# SEGMENTOVKA_I2C.net
KiCad netlist of a schematic drawn in EAGLE
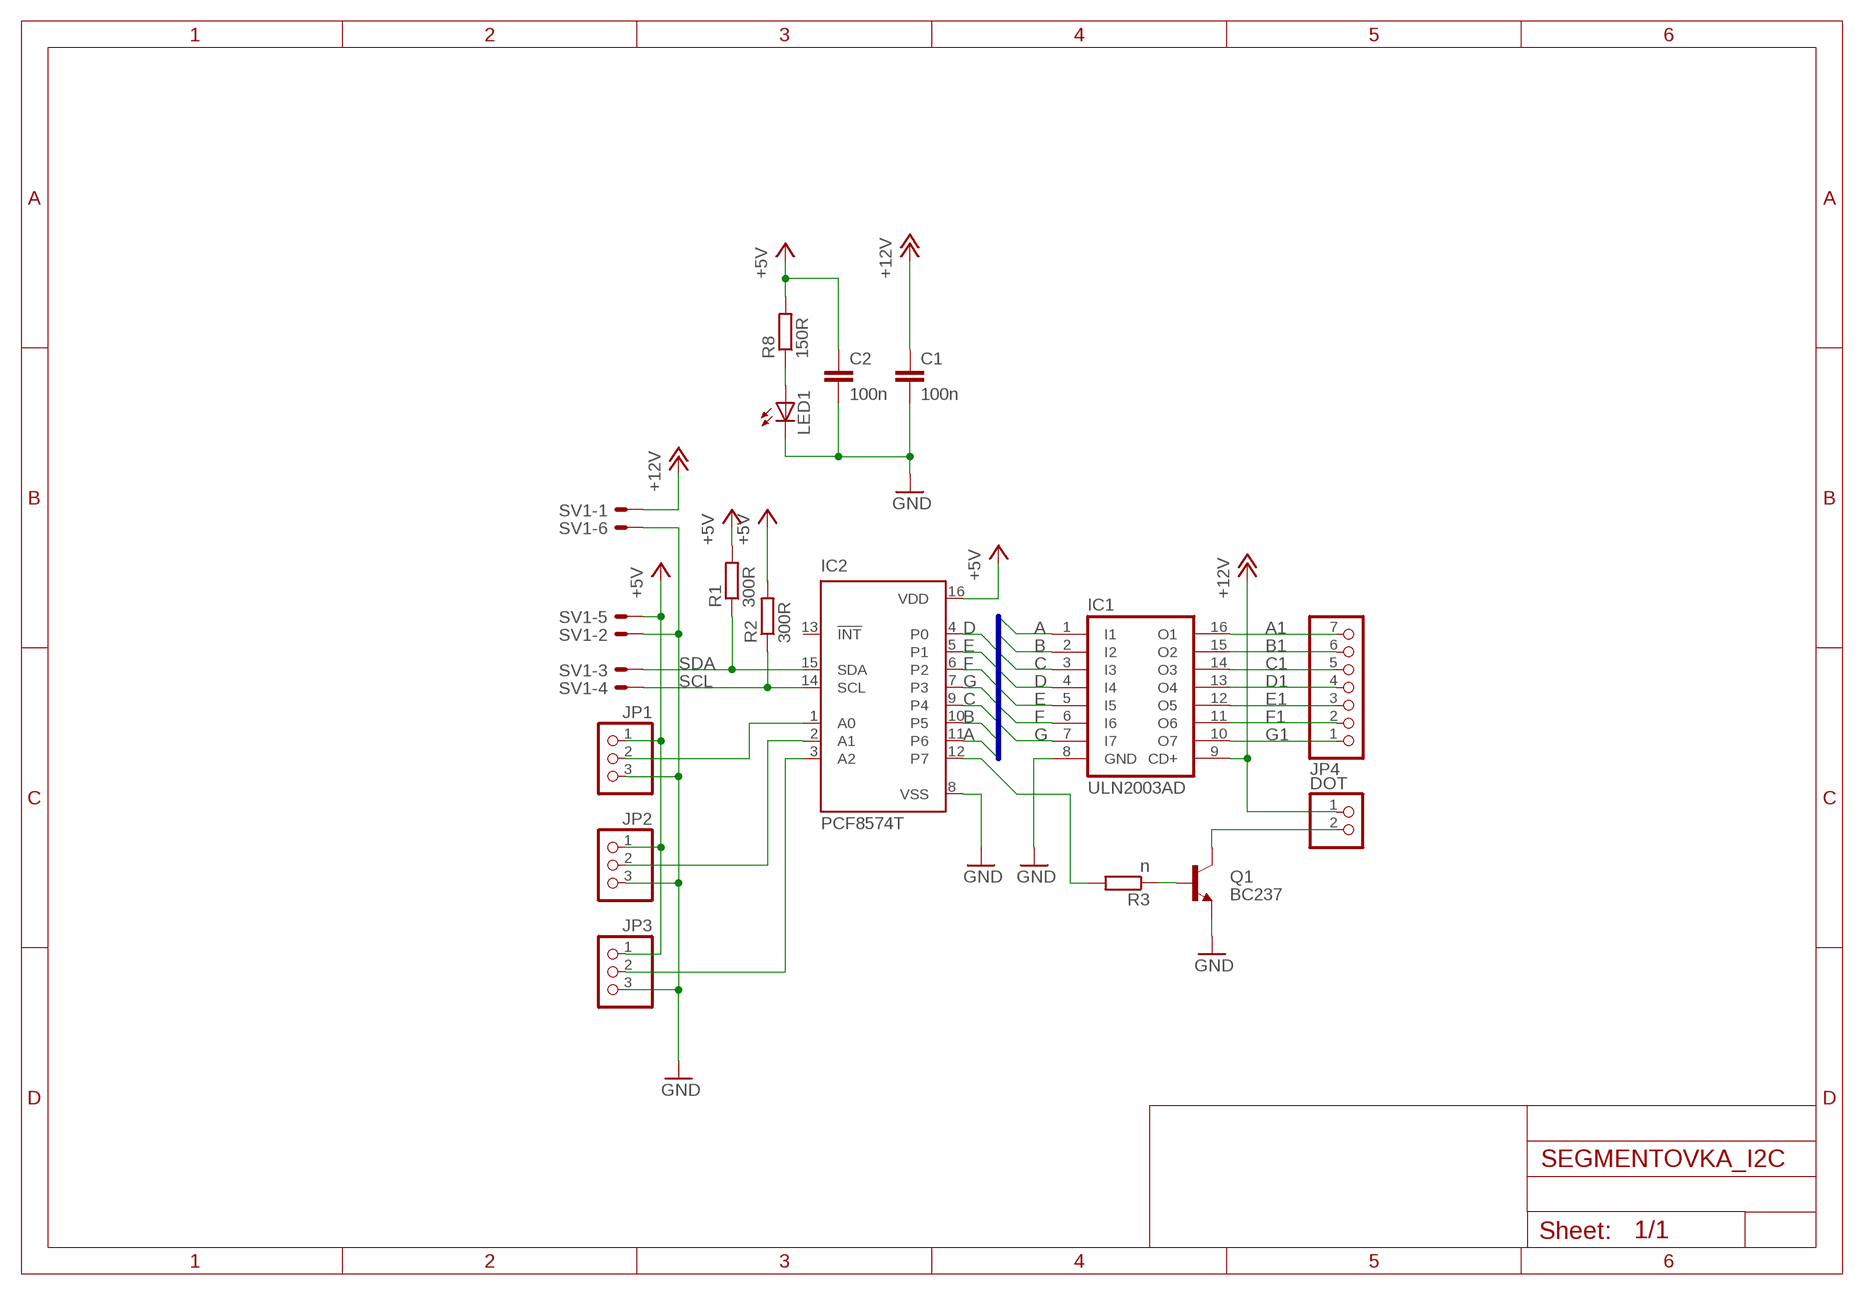
[diagram p0: schematic, sheet 1]

(export (version "E")
  (design (tool "Eeschema 10.0.6"))
  (components
    (comp (ref "C1")
      (value "100n")
      (footprint "eagle-import:C0603")
      (libsource (lib "eagle-import") (part "C-EUC0603"))
    )
    (comp (ref "C2")
      (value "100n")
      (footprint "eagle-import:C0603")
      (libsource (lib "eagle-import") (part "C-EUC0603"))
    )
    (comp (ref "DOT")
      (value "PINHD-1X2")
      (footprint "eagle-import:1X02")
      (libsource (lib "eagle-import") (part "PINHD-1X2"))
    )
    (comp (ref "IC1")
      (value "ULN2003AD")
      (footprint "eagle-import:SO16")
      (libsource (lib "eagle-import") (part "ULN2003AD"))
    )
    (comp (ref "IC2")
      (value "PCF8574T")
      (footprint "eagle-import:SO16W")
      (fields (field (name "MPN") "PCF8574T/3,512"))
      (libsource (lib "eagle-import") (part "PCF8574T"))
    )
    (comp (ref "JP1")
      (value "PINHD-1X3")
      (footprint "eagle-import:1X03")
      (libsource (lib "eagle-import") (part "PINHD-1X3"))
    )
    (comp (ref "JP2")
      (value "PINHD-1X3")
      (footprint "eagle-import:1X03")
      (libsource (lib "eagle-import") (part "PINHD-1X3"))
    )
    (comp (ref "JP3")
      (value "PINHD-1X3")
      (footprint "eagle-import:1X03")
      (libsource (lib "eagle-import") (part "PINHD-1X3"))
    )
    (comp (ref "JP4")
      (value "PINHD-1X7")
      (footprint "eagle-import:1X07")
      (libsource (lib "eagle-import") (part "PINHD-1X7"))
    )
    (comp (ref "LED1")
      (value "LEDCHIP-LED0603")
      (footprint "eagle-import:CHIP-LED0603")
      (libsource (lib "eagle-import") (part "LEDCHIP-LED0603"))
    )
    (comp (ref "Q1")
      (value "BC237")
      (footprint "eagle-import:TO92")
      (libsource (lib "eagle-import") (part "BC237"))
    )
    (comp (ref "R1")
      (value "300R")
      (footprint "eagle-import:R0603")
      (libsource (lib "eagle-import") (part "R-EU_R0603"))
    )
    (comp (ref "R2")
      (value "300R")
      (footprint "eagle-import:R0603")
      (libsource (lib "eagle-import") (part "R-EU_R0603"))
    )
    (comp (ref "R3")
      (value "n")
      (footprint "eagle-import:R0603")
      (libsource (lib "eagle-import") (part "R-EU_R0603"))
    )
    (comp (ref "R8")
      (value "150R")
      (footprint "eagle-import:R0603")
      (libsource (lib "eagle-import") (part "R-EU_R0603"))
    )
    (comp (ref "SV1")
      (value "ML6E")
      (footprint "eagle-import:ML6")
      (libsource (lib "eagle-import") (part "ML6E"))
    )
  )
  (nets
    (net (code "1") (name "+5V") (class "Default")
      (node (ref "C2") (pin "1") (pinfunction "1_1") (pintype "passive"))
      (node (ref "IC2") (pin "16") (pinfunction "VDD_16") (pintype "power_in"))
      (node (ref "JP1") (pin "1") (pinfunction "1_1") (pintype "passive"))
      (node (ref "JP2") (pin "1") (pinfunction "1_1") (pintype "passive"))
      (node (ref "JP3") (pin "1") (pinfunction "1_1") (pintype "passive"))
      (node (ref "R1") (pin "2") (pinfunction "2_2") (pintype "passive"))
      (node (ref "R2") (pin "2") (pinfunction "2_2") (pintype "passive"))
      (node (ref "R8") (pin "2") (pinfunction "2_2") (pintype "passive"))
      (node (ref "SV1") (pin "5") (pinfunction "S_5") (pintype "passive"))
    )
    (net (code "2") (name "+12V") (class "Default")
      (node (ref "C1") (pin "1") (pinfunction "1_1") (pintype "passive"))
      (node (ref "DOT") (pin "1") (pinfunction "1_1") (pintype "passive"))
      (node (ref "IC1") (pin "9") (pinfunction "CD+_9") (pintype "passive"))
      (node (ref "SV1") (pin "1") (pinfunction "S_1") (pintype "passive"))
    )
    (net (code "3") (name "/A") (class "Default")
      (node (ref "IC1") (pin "1") (pinfunction "I1_1") (pintype "input"))
      (node (ref "IC2") (pin "11") (pinfunction "P6_11") (pintype "bidirectional"))
    )
    (net (code "4") (name "/A1") (class "Default")
      (node (ref "IC1") (pin "16") (pinfunction "O1_16") (pintype "open_collector"))
      (node (ref "JP4") (pin "7") (pinfunction "7_7") (pintype "passive"))
    )
    (net (code "5") (name "/B") (class "Default")
      (node (ref "IC1") (pin "2") (pinfunction "I2_2") (pintype "input"))
      (node (ref "IC2") (pin "10") (pinfunction "P5_10") (pintype "bidirectional"))
    )
    (net (code "6") (name "/B1") (class "Default")
      (node (ref "IC1") (pin "15") (pinfunction "O2_15") (pintype "open_collector"))
      (node (ref "JP4") (pin "6") (pinfunction "6_6") (pintype "passive"))
    )
    (net (code "7") (name "/C") (class "Default")
      (node (ref "IC1") (pin "3") (pinfunction "I3_3") (pintype "input"))
      (node (ref "IC2") (pin "9") (pinfunction "P4_9") (pintype "bidirectional"))
    )
    (net (code "8") (name "/C1") (class "Default")
      (node (ref "IC1") (pin "14") (pinfunction "O3_14") (pintype "open_collector"))
      (node (ref "JP4") (pin "5") (pinfunction "5_5") (pintype "passive"))
    )
    (net (code "9") (name "/D") (class "Default")
      (node (ref "IC1") (pin "4") (pinfunction "I4_4") (pintype "input"))
      (node (ref "IC2") (pin "4") (pinfunction "P0_4") (pintype "bidirectional"))
    )
    (net (code "10") (name "/D1") (class "Default")
      (node (ref "IC1") (pin "13") (pinfunction "O4_13") (pintype "open_collector"))
      (node (ref "JP4") (pin "4") (pinfunction "4_4") (pintype "passive"))
    )
    (net (code "11") (name "/E") (class "Default")
      (node (ref "IC1") (pin "5") (pinfunction "I5_5") (pintype "input"))
      (node (ref "IC2") (pin "5") (pinfunction "P1_5") (pintype "bidirectional"))
    )
    (net (code "12") (name "/E1") (class "Default")
      (node (ref "IC1") (pin "12") (pinfunction "O5_12") (pintype "open_collector"))
      (node (ref "JP4") (pin "3") (pinfunction "3_3") (pintype "passive"))
    )
    (net (code "13") (name "/F") (class "Default")
      (node (ref "IC1") (pin "6") (pinfunction "I6_6") (pintype "input"))
      (node (ref "IC2") (pin "6") (pinfunction "P2_6") (pintype "bidirectional"))
    )
    (net (code "14") (name "/F1") (class "Default")
      (node (ref "IC1") (pin "11") (pinfunction "O6_11") (pintype "open_collector"))
      (node (ref "JP4") (pin "2") (pinfunction "2_2") (pintype "passive"))
    )
    (net (code "15") (name "/G") (class "Default")
      (node (ref "IC1") (pin "7") (pinfunction "I7_7") (pintype "input"))
      (node (ref "IC2") (pin "7") (pinfunction "P3_7") (pintype "bidirectional"))
    )
    (net (code "16") (name "/G1") (class "Default")
      (node (ref "IC1") (pin "10") (pinfunction "O7_10") (pintype "open_collector"))
      (node (ref "JP4") (pin "1") (pinfunction "1_1") (pintype "passive"))
    )
    (net (code "17") (name "/SCL") (class "Default")
      (node (ref "IC2") (pin "14") (pinfunction "SCL_14") (pintype "input"))
      (node (ref "R2") (pin "1") (pinfunction "1_1") (pintype "passive"))
      (node (ref "SV1") (pin "4") (pinfunction "S_4") (pintype "passive"))
    )
    (net (code "18") (name "/SDA") (class "Default")
      (node (ref "IC2") (pin "15") (pinfunction "SDA_15") (pintype "bidirectional"))
      (node (ref "R1") (pin "1") (pinfunction "1_1") (pintype "passive"))
      (node (ref "SV1") (pin "3") (pinfunction "S_3") (pintype "passive"))
    )
    (net (code "19") (name "GND") (class "Default")
      (node (ref "C1") (pin "2") (pinfunction "2_2") (pintype "passive"))
      (node (ref "C2") (pin "2") (pinfunction "2_2") (pintype "passive"))
      (node (ref "IC1") (pin "8") (pinfunction "GND_8") (pintype "power_in"))
      (node (ref "IC2") (pin "8") (pinfunction "VSS_8") (pintype "power_in"))
      (node (ref "JP1") (pin "3") (pinfunction "3_3") (pintype "passive"))
      (node (ref "JP2") (pin "3") (pinfunction "3_3") (pintype "passive"))
      (node (ref "JP3") (pin "3") (pinfunction "3_3") (pintype "passive"))
      (node (ref "LED1") (pin "C") (pinfunction "C_C") (pintype "passive"))
      (node (ref "Q1") (pin "1") (pinfunction "E_1") (pintype "passive"))
      (node (ref "SV1") (pin "2") (pinfunction "S_2") (pintype "passive"))
      (node (ref "SV1") (pin "6") (pinfunction "S_6") (pintype "passive"))
    )
    (net (code "20") (name "Net-(IC2-A0)") (class "Default")
      (node (ref "IC2") (pin "1") (pinfunction "A0_1") (pintype "input"))
      (node (ref "JP1") (pin "2") (pinfunction "2_2") (pintype "passive"))
    )
    (net (code "21") (name "Net-(IC2-A1)") (class "Default")
      (node (ref "IC2") (pin "2") (pinfunction "A1_2") (pintype "input"))
      (node (ref "JP2") (pin "2") (pinfunction "2_2") (pintype "passive"))
    )
    (net (code "22") (name "Net-(IC2-A2)") (class "Default")
      (node (ref "IC2") (pin "3") (pinfunction "A2_3") (pintype "input"))
      (node (ref "JP3") (pin "2") (pinfunction "2_2") (pintype "passive"))
    )
    (net (code "23") (name "Net-(IC2-P7)") (class "Default")
      (node (ref "IC2") (pin "12") (pinfunction "P7_12") (pintype "bidirectional"))
      (node (ref "R3") (pin "2") (pinfunction "2_2") (pintype "passive"))
    )
    (net (code "24") (name "Net-(LED1-PadA)") (class "Default")
      (node (ref "LED1") (pin "A") (pinfunction "A_A") (pintype "passive"))
      (node (ref "R8") (pin "1") (pinfunction "1_1") (pintype "passive"))
    )
    (net (code "25") (name "Net-(Q1-B)") (class "Default")
      (node (ref "Q1") (pin "2") (pinfunction "B_2") (pintype "passive"))
      (node (ref "R3") (pin "1") (pinfunction "1_1") (pintype "passive"))
    )
    (net (code "26") (name "Net-(Q1-C)") (class "Default")
      (node (ref "DOT") (pin "2") (pinfunction "2_2") (pintype "passive"))
      (node (ref "Q1") (pin "3") (pinfunction "C_3") (pintype "passive"))
    )
    (net (code "27") (name "unconnected-(IC2-~{INT}-Pad13)") (class "Default")
      (node (ref "IC2") (pin "13") (pinfunction "~{INT}_13") (pintype "output"))
    )
  )
)
